# FM-Super-Regenerative-Tuner-ForcedQuench.net
KiCad netlist of a schematic drawn in EAGLE
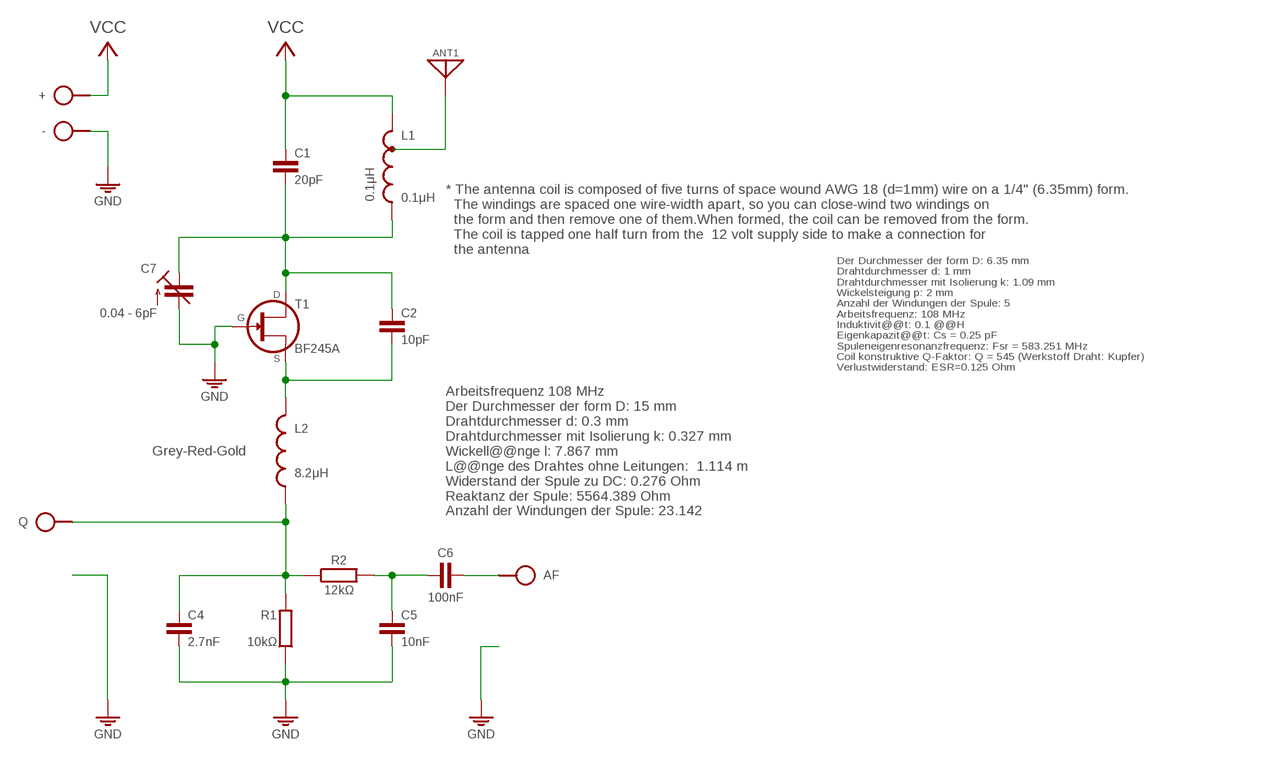
[diagram p0: schematic, sheet 1]

(export (version "E")
  (design (tool "Eeschema 10.0.6"))
  (components
    (comp (ref "+")
      (value "SPAD")
      (footprint "eagle-import:SPAD")
      (libsource (lib "eagle-import") (part "SPAD"))
    )
    (comp (ref "-")
      (value "SPAD")
      (footprint "eagle-import:SPAD")
      (libsource (lib "eagle-import") (part "SPAD"))
    )
    (comp (ref "AF")
      (value "SPAD")
      (footprint "eagle-import:SPAD")
      (libsource (lib "eagle-import") (part "SPAD"))
    )
    (comp (ref "ANT1")
      (value "ANT")
      (footprint "eagle-import:SPAD")
      (libsource (lib "eagle-import") (part "ANT"))
    )
    (comp (ref "C1")
      (value "20pF")
      (footprint "eagle-import:C025-015X024")
      (libsource (lib "eagle-import") (part "C025-015X024"))
    )
    (comp (ref "C2")
      (value "10pF")
      (footprint "eagle-import:C025-015X024")
      (libsource (lib "eagle-import") (part "C025-015X024"))
    )
    (comp (ref "C4")
      (value "2.7nF")
      (footprint "eagle-import:C050-020X044")
      (libsource (lib "eagle-import") (part "C050-020X044"))
    )
    (comp (ref "C5")
      (value "10nF")
      (footprint "eagle-import:C025-015X024")
      (libsource (lib "eagle-import") (part "C025-015X024"))
    )
    (comp (ref "C6")
      (value "100nF")
      (footprint "eagle-import:C050-020X044")
      (libsource (lib "eagle-import") (part "C-H050-020X044"))
    )
    (comp (ref "C7")
      (value "0.04 - 6pF")
      (footprint "eagle-import:CTRIMTZ03")
      (libsource (lib "eagle-import") (part "C-TR-PH20127-TZ03"))
    )
    (comp (ref "L1")
      (value "0.1μH")
      (footprint "eagle-import:L-08-7_8-TAP1")
      (libsource (lib "eagle-import") (part "L-TAP1L-08-7/5H"))
    )
    (comp (ref "L2")
      (value "8.2μH")
      (footprint "eagle-import:L-04_7-V")
      (libsource (lib "eagle-import") (part "L04/7-V"))
    )
    (comp (ref "Q")
      (value "SPAD")
      (footprint "eagle-import:SPAD")
      (libsource (lib "eagle-import") (part "SPAD"))
    )
    (comp (ref "R1")
      (value "10kΩ")
      (footprint "eagle-import:0204_7")
      (libsource (lib "eagle-import") (part "R0204/7"))
    )
    (comp (ref "R2")
      (value "12kΩ")
      (footprint "eagle-import:0204_7")
      (libsource (lib "eagle-import") (part "R-H0204/7"))
    )
    (comp (ref "T1")
      (value "BF245A")
      (footprint "eagle-import:TO92-GSD")
      (libsource (lib "eagle-import") (part "BF245BTO92"))
    )
  )
  (nets
    (net (code "1") (name "GND") (class "Default")
      (node (ref "-") (pin "1") (pinfunction "P$1_1") (pintype "passive"))
      (node (ref "C4") (pin "2") (pinfunction "2_2") (pintype "passive"))
      (node (ref "C5") (pin "2") (pinfunction "2_2") (pintype "passive"))
      (node (ref "C7") (pin "1") (pinfunction "A_1") (pintype "passive"))
      (node (ref "R1") (pin "1") (pinfunction "2_1") (pintype "passive"))
      (node (ref "T1") (pin "1") (pinfunction "G_1") (pintype "passive"))
    )
    (net (code "2") (name "Net-(AF-P$1)") (class "Default")
      (node (ref "AF") (pin "1") (pinfunction "P$1_1") (pintype "passive"))
      (node (ref "C6") (pin "2") (pinfunction "2_2") (pintype "passive"))
    )
    (net (code "3") (name "Net-(C5-Pad1)") (class "Default")
      (node (ref "C5") (pin "1") (pinfunction "1_1") (pintype "passive"))
      (node (ref "C6") (pin "1") (pinfunction "1_1") (pintype "passive"))
      (node (ref "R2") (pin "2") (pinfunction "2_2") (pintype "passive"))
    )
    (net (code "4") (name "Net-(C7-E)") (class "Default")
      (node (ref "C1") (pin "2") (pinfunction "2_2") (pintype "passive"))
      (node (ref "C2") (pin "1") (pinfunction "1_1") (pintype "passive"))
      (node (ref "C7") (pin "2") (pinfunction "E_2") (pintype "passive"))
      (node (ref "L1") (pin "2") (pinfunction "2_2") (pintype "passive"))
      (node (ref "T1") (pin "3") (pinfunction "D_3") (pintype "passive"))
    )
    (net (code "5") (name "Net-(L1-T)") (class "Default")
      (node (ref "ANT1") (pin "1") (pinfunction "1_1") (pintype "output"))
      (node (ref "L1") (pin "3") (pinfunction "T_3") (pintype "passive"))
    )
    (net (code "6") (name "Net-(Q-P$1)") (class "Default")
      (node (ref "C4") (pin "1") (pinfunction "1_1") (pintype "passive"))
      (node (ref "L2") (pin "2") (pinfunction "2_2") (pintype "passive"))
      (node (ref "Q") (pin "1") (pinfunction "P$1_1") (pintype "passive"))
      (node (ref "R1") (pin "2") (pinfunction "1_2") (pintype "passive"))
      (node (ref "R2") (pin "1") (pinfunction "1_1") (pintype "passive"))
    )
    (net (code "7") (name "Net-(T1-S)") (class "Default")
      (node (ref "C2") (pin "2") (pinfunction "2_2") (pintype "passive"))
      (node (ref "L2") (pin "1") (pinfunction "1_1") (pintype "passive"))
      (node (ref "T1") (pin "2") (pinfunction "S_2") (pintype "passive"))
    )
    (net (code "8") (name "VCC") (class "Default")
      (node (ref "+") (pin "1") (pinfunction "P$1_1") (pintype "passive"))
      (node (ref "C1") (pin "1") (pinfunction "1_1") (pintype "passive"))
      (node (ref "L1") (pin "1") (pinfunction "1_1") (pintype "passive"))
    )
  )
)
